# Energy_harvesting.net
KiCad netlist of a schematic drawn in Altium Designer
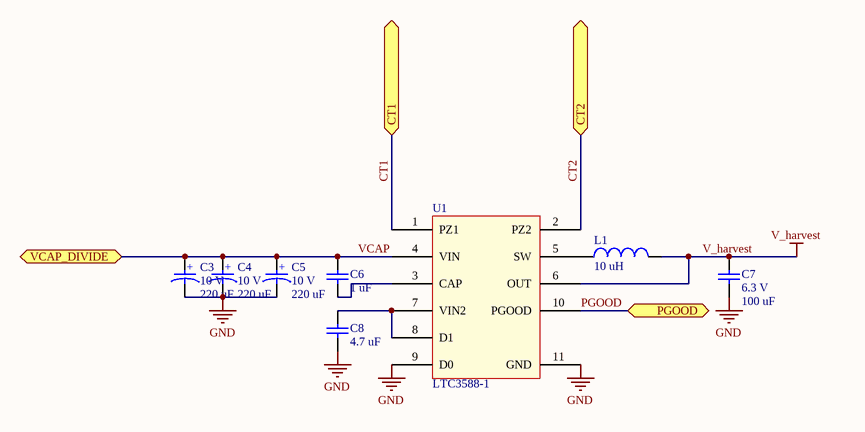
[diagram p0: Energy_harvesting.SchDoc]

(export (version "E")
  (design (tool "Eeschema 10.0.6"))
  (components
    (comp (ref "C3")
      (value "220 uF")
      (footprint "2312")
      (description "Tantalum capacitor, 220 uF, 10 V, 2312 package")
      (fields
        (field (name "TOLERANCE") "10%")
        (field (name "VOLTAGE RATED") "10 V")
        (field (name "Comment") "Tantalum capacitor")
      )
      (libsource (lib "rlc") (part "C_220u_10V_2312_tantalum"))
    )
    (comp (ref "C4")
      (value "220 uF")
      (footprint "2312")
      (description "Tantalum capacitor, 220 uF, 10 V, 2312 package")
      (fields
        (field (name "TOLERANCE") "10%")
        (field (name "VOLTAGE RATED") "10 V")
        (field (name "Comment") "Tantalum capacitor")
      )
      (libsource (lib "rlc") (part "C_220u_10V_2312_tantalum"))
    )
    (comp (ref "C5")
      (value "220 uF")
      (footprint "2312")
      (description "Tantalum capacitor, 220 uF, 10 V, 2312 package")
      (fields
        (field (name "TOLERANCE") "10%")
        (field (name "VOLTAGE RATED") "10 V")
        (field (name "Comment") "Tantalum capacitor")
      )
      (libsource (lib "rlc") (part "C_220u_10V_2312_tantalum"))
    )
    (comp (ref "C6")
      (value "1 uF")
      (footprint "0402")
      (description "Ceramic capacitor, 1 uF, 16V, 0402 package")
      (fields (field (name "TOLERANCE") "10%") (field (name "Comment") "Ceramic capacitor"))
      (libsource (lib "rlc") (part "C_1u_16V_0402_ceramic"))
    )
    (comp (ref "C7")
      (value "100 uF")
      (footprint "1206")
      (description "Ceramic capacitor, 100 uF, 6.3 V, 1206 package")
      (fields
        (field (name "VOLTAGE RATED") "6.3 V")
        (field (name "TOLERANCE") "20%")
        (field (name "Comment") "Ceramic capacitor")
      )
      (libsource (lib "rlc") (part "C_100u_6.3V_1206_ceramic"))
    )
    (comp (ref "C8")
      (value "4.7 uF")
      (footprint "0603")
      (description "Ceramic capacitor, 4.7u, 10V, 0603 package")
      (fields (field (name "TOLERANCE") "20%") (field (name "Comment") "Ceramic capacitor"))
      (libsource (lib "rlc") (part "C_4.7u_10V_0603_ceramic"))
    )
    (comp (ref "L1")
      (value "10 uH")
      (footprint "CDRH2D18")
      (description "Chip inductor, 10 uH,  1A, 180 mOhm")
      (fields (field (name "TOLERANCE") "30%") (field (name "Comment") "Chip inductor"))
      (libsource (lib "rlc") (part "L_10uH_1A_180m"))
    )
    (comp (ref "U1")
      (value "LTC3588-1")
      (footprint "QFN-10")
      (description "Piezoelectric Energy   Harvesting Power Supply")
      (libsource (lib "voltage_regulators") (part "LTC3588-1"))
    )
  )
  (nets
    (net (code "1") (name "/CT1") (class "Default")
      (node (ref "U1") (pin "1") (pinfunction "PZ1_1") (pintype "passive"))
    )
    (net (code "2") (name "/CT2") (class "Default")
      (node (ref "U1") (pin "2") (pinfunction "PZ2_2") (pintype "passive"))
    )
    (net (code "3") (name "/PGOOD") (class "Default")
      (node (ref "U1") (pin "10") (pinfunction "PGOOD_10") (pintype "passive"))
    )
    (net (code "4") (name "/VCAP") (class "Default")
      (node (ref "C3") (pin "1") (pintype "passive"))
      (node (ref "C4") (pin "1") (pintype "passive"))
      (node (ref "C5") (pin "1") (pintype "passive"))
      (node (ref "C6") (pin "1") (pintype "passive"))
      (node (ref "U1") (pin "4") (pinfunction "VIN_4") (pintype "passive"))
    )
    (net (code "5") (name "GND") (class "Default")
      (node (ref "C3") (pin "2") (pintype "passive"))
      (node (ref "C4") (pin "2") (pintype "passive"))
      (node (ref "C5") (pin "2") (pintype "passive"))
      (node (ref "C7") (pin "2") (pintype "passive"))
      (node (ref "C8") (pin "2") (pintype "passive"))
      (node (ref "U1") (pin "11") (pinfunction "GND_11") (pintype "passive"))
      (node (ref "U1") (pin "9") (pinfunction "D0_9") (pintype "passive"))
    )
    (net (code "6") (name "Net-(U1-CAP)") (class "Default")
      (node (ref "C6") (pin "2") (pintype "passive"))
      (node (ref "U1") (pin "3") (pinfunction "CAP_3") (pintype "passive"))
    )
    (net (code "7") (name "Net-(U1-D1)") (class "Default")
      (node (ref "C8") (pin "1") (pintype "passive"))
      (node (ref "U1") (pin "7") (pinfunction "VIN2_7") (pintype "passive"))
      (node (ref "U1") (pin "8") (pinfunction "D1_8") (pintype "passive"))
    )
    (net (code "8") (name "Net-(U1-SW)") (class "Default")
      (node (ref "L1") (pin "2") (pintype "passive"))
      (node (ref "U1") (pin "5") (pinfunction "SW_5") (pintype "passive"))
    )
    (net (code "9") (name "V_harvest") (class "Default")
      (node (ref "C7") (pin "1") (pintype "passive"))
      (node (ref "L1") (pin "1") (pintype "passive"))
      (node (ref "U1") (pin "6") (pinfunction "OUT_6") (pintype "passive"))
    )
  )
)
